# PIC_POWER_MISC.net
KiCad netlist of a schematic drawn in Altium Designer
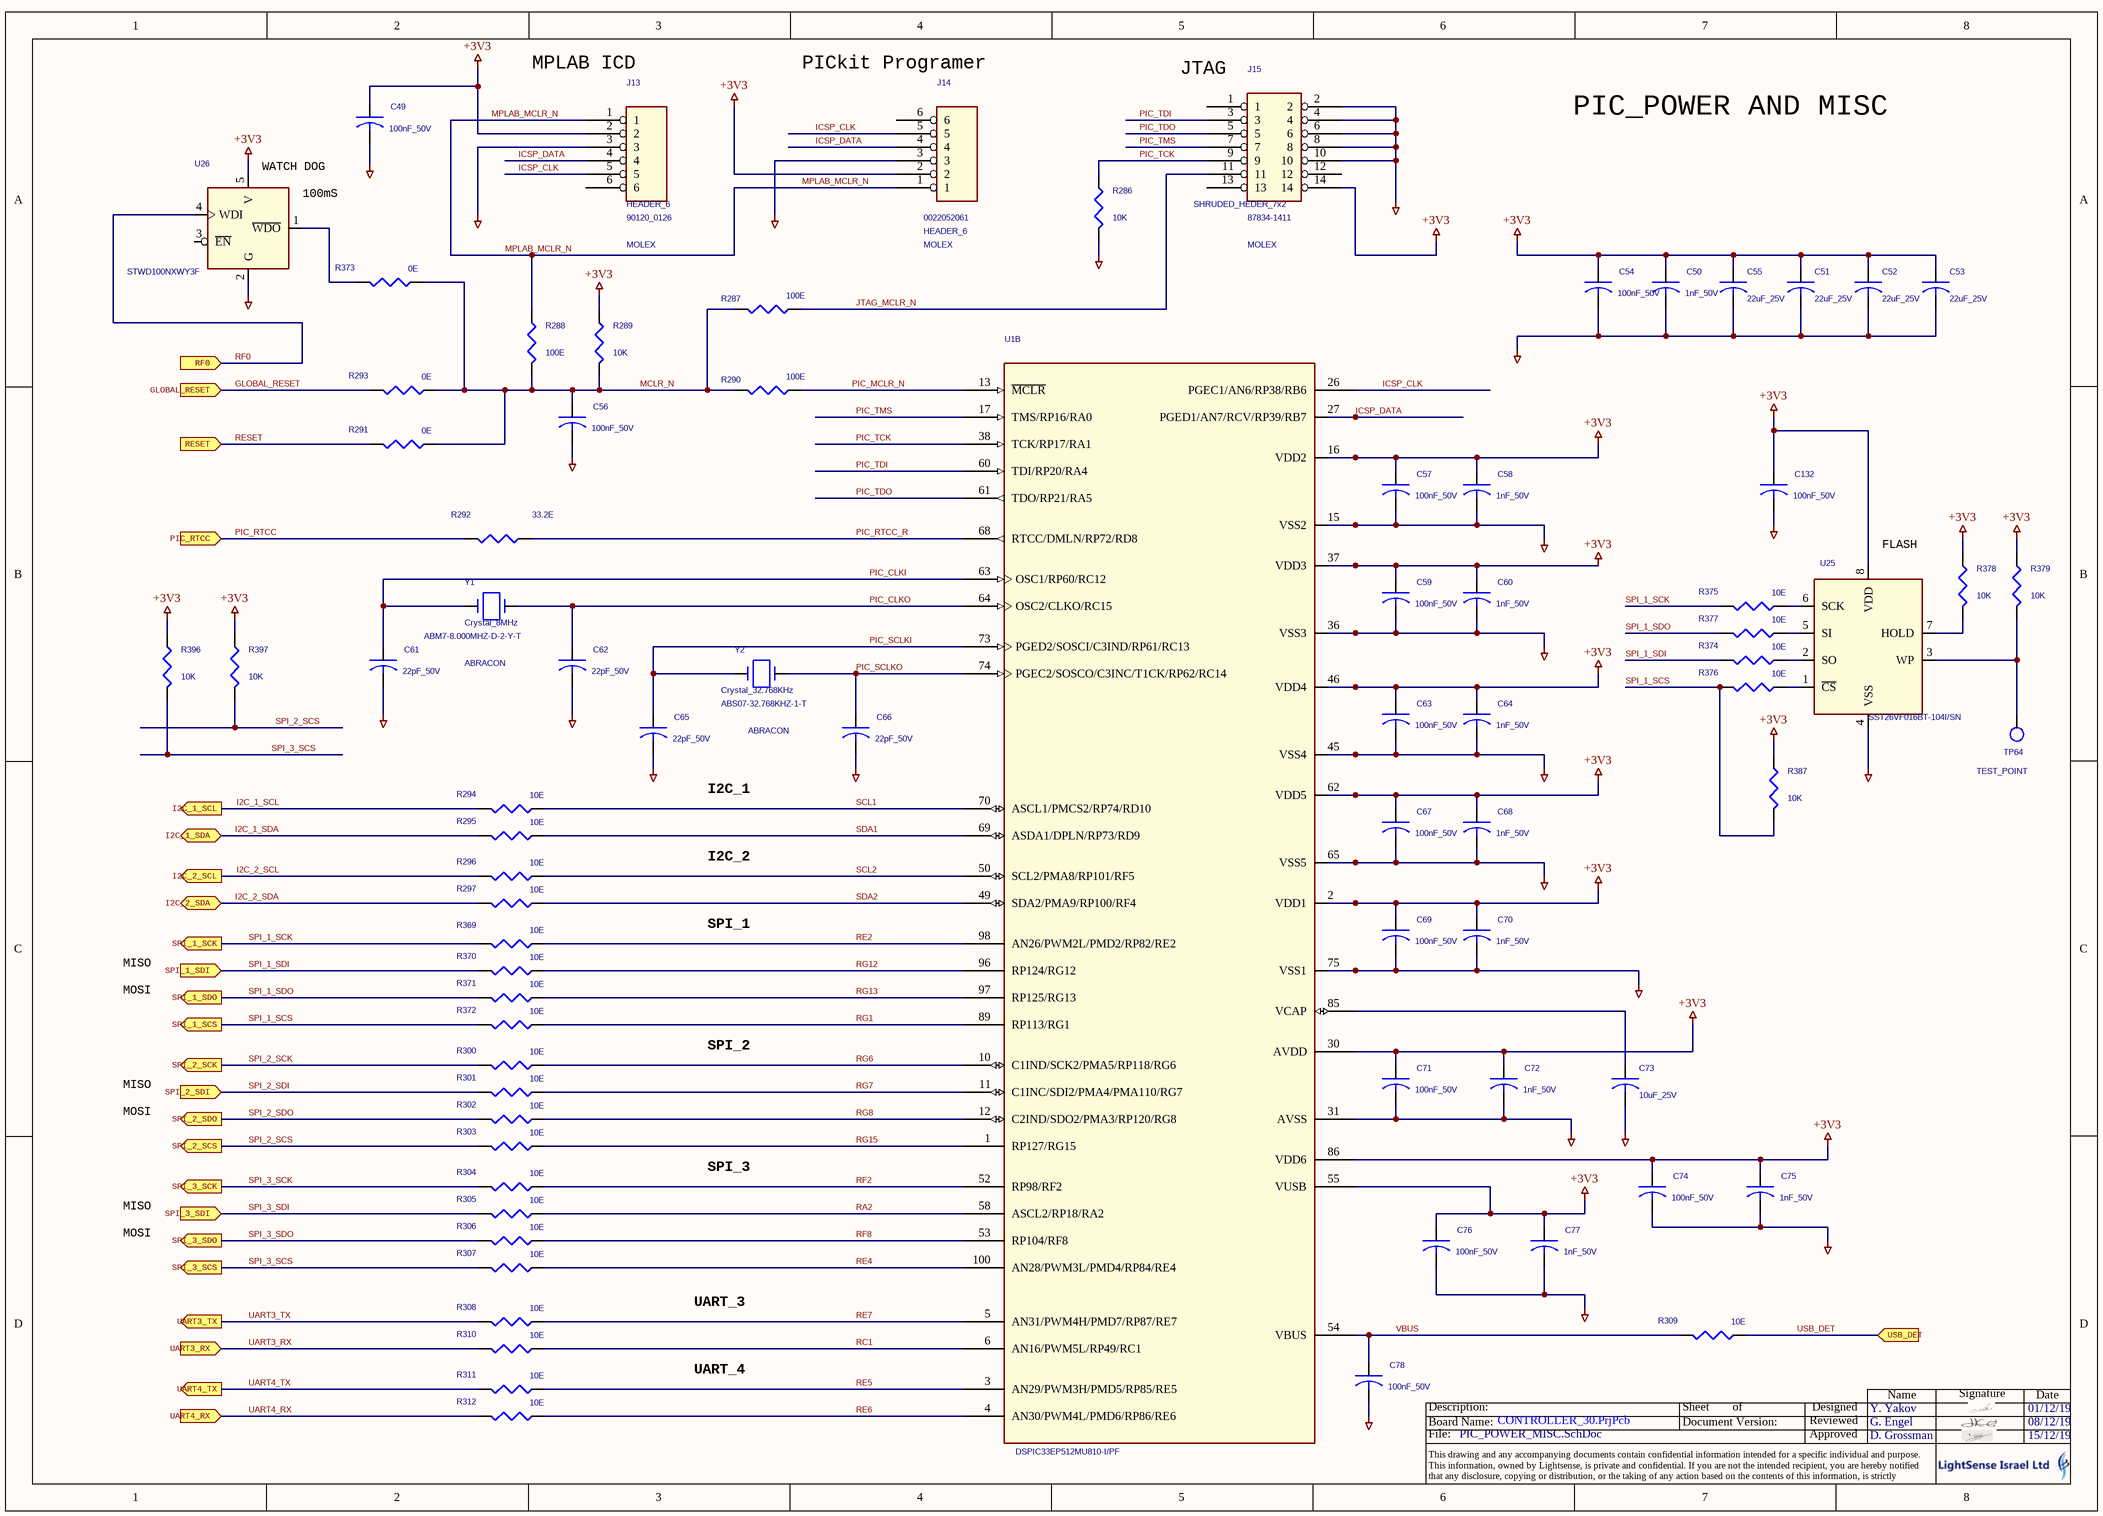
[diagram p0: PIC_POWER_MISC.SchDoc]

(export (version "E")
  (design (tool "Eeschema 10.0.6"))
  (components
    (comp (ref "C49")
      (value "100nF_50V")
      (footprint "0603")
      (description "CAP_SMT_0603_50V_X7R_10%")
      (fields (field (name "MFG") "KEMET"))
      (libsource (lib "*") (part "C"))
    )
    (comp (ref "C50")
      (value "1nF_50V")
      (footprint "0603")
      (description "CAP_SMT_0603_50V_X7R_10%")
      (fields (field (name "MFG") "KEMET"))
      (libsource (lib "*") (part "C"))
    )
    (comp (ref "C51")
      (value "22uF_25V")
      (footprint "1210")
      (description "CAP_SMT_1210_25V_X7R_10%")
      (fields (field (name "MFG") "KEMET"))
      (libsource (lib "*") (part "C"))
    )
    (comp (ref "C52")
      (value "22uF_25V")
      (footprint "1210")
      (description "CAP_SMT_1210_25V_X7R_10%")
      (fields (field (name "MFG") "KEMET"))
      (libsource (lib "*") (part "C"))
    )
    (comp (ref "C53")
      (value "22uF_25V")
      (footprint "1210")
      (description "CAP_SMT_1210_25V_X7R_10%")
      (fields (field (name "MFG") "KEMET"))
      (libsource (lib "*") (part "C"))
    )
    (comp (ref "C54")
      (value "100nF_50V")
      (footprint "0603")
      (description "CAP_SMT_0603_50V_X7R_10%")
      (fields (field (name "MFG") "KEMET"))
      (libsource (lib "*") (part "C"))
    )
    (comp (ref "C55")
      (value "22uF_25V")
      (footprint "1210")
      (description "CAP_SMT_1210_25V_X7R_10%")
      (fields (field (name "MFG") "KEMET"))
      (libsource (lib "*") (part "C"))
    )
    (comp (ref "C56")
      (value "100nF_50V")
      (footprint "0603")
      (description "CAP_SMT_0603_50V_X7R_10%")
      (fields (field (name "MFG") "KEMET"))
      (libsource (lib "*") (part "C"))
    )
    (comp (ref "C57")
      (value "100nF_50V")
      (footprint "0603")
      (description "CAP_SMT_0603_50V_X7R_10%")
      (fields (field (name "MFG") "KEMET"))
      (libsource (lib "*") (part "C"))
    )
    (comp (ref "C58")
      (value "1nF_50V")
      (footprint "0603")
      (description "CAP_SMT_0603_50V_X7R_10%")
      (fields (field (name "MFG") "KEMET"))
      (libsource (lib "*") (part "C"))
    )
    (comp (ref "C59")
      (value "100nF_50V")
      (footprint "0603")
      (description "CAP_SMT_0603_50V_X7R_10%")
      (fields (field (name "MFG") "KEMET"))
      (libsource (lib "*") (part "C"))
    )
    (comp (ref "C60")
      (value "1nF_50V")
      (footprint "0603")
      (description "CAP_SMT_0603_50V_X7R_10%")
      (fields (field (name "MFG") "KEMET"))
      (libsource (lib "*") (part "C"))
    )
    (comp (ref "C61")
      (value "22pF_50V")
      (footprint "0603")
      (description "CAP_SMT_0603_50V_COG_10%")
      (fields (field (name "MFG") "KEMET"))
      (libsource (lib "*") (part "C"))
    )
    (comp (ref "C62")
      (value "22pF_50V")
      (footprint "0603")
      (description "CAP_SMT_0603_50V_COG_10%")
      (fields (field (name "MFG") "KEMET"))
      (libsource (lib "*") (part "C"))
    )
    (comp (ref "C63")
      (value "100nF_50V")
      (footprint "0603")
      (description "CAP_SMT_0603_50V_X7R_10%")
      (fields (field (name "MFG") "KEMET"))
      (libsource (lib "*") (part "C"))
    )
    (comp (ref "C64")
      (value "1nF_50V")
      (footprint "0603")
      (description "CAP_SMT_0603_50V_X7R_10%")
      (fields (field (name "MFG") "KEMET"))
      (libsource (lib "*") (part "C"))
    )
    (comp (ref "C65")
      (value "22pF_50V")
      (footprint "0603")
      (description "CAP_SMT_0603_50V_COG_10%")
      (fields (field (name "MFG") "KEMET"))
      (libsource (lib "*") (part "C"))
    )
    (comp (ref "C66")
      (value "22pF_50V")
      (footprint "0603")
      (description "CAP_SMT_0603_50V_COG_10%")
      (fields (field (name "MFG") "KEMET"))
      (libsource (lib "*") (part "C"))
    )
    (comp (ref "C67")
      (value "100nF_50V")
      (footprint "0603")
      (description "CAP_SMT_0603_50V_X7R_10%")
      (fields (field (name "MFG") "KEMET"))
      (libsource (lib "*") (part "C"))
    )
    (comp (ref "C68")
      (value "1nF_50V")
      (footprint "0603")
      (description "CAP_SMT_0603_50V_X7R_10%")
      (fields (field (name "MFG") "KEMET"))
      (libsource (lib "*") (part "C"))
    )
    (comp (ref "C69")
      (value "100nF_50V")
      (footprint "0603")
      (description "CAP_SMT_0603_50V_X7R_10%")
      (fields (field (name "MFG") "KEMET"))
      (libsource (lib "*") (part "C"))
    )
    (comp (ref "C70")
      (value "1nF_50V")
      (footprint "0603")
      (description "CAP_SMT_0603_50V_X7R_10%")
      (fields (field (name "MFG") "KEMET"))
      (libsource (lib "*") (part "C"))
    )
    (comp (ref "C71")
      (value "100nF_50V")
      (footprint "0603")
      (description "CAP_SMT_0603_50V_X7R_10%")
      (fields (field (name "MFG") "KEMET"))
      (libsource (lib "*") (part "C"))
    )
    (comp (ref "C72")
      (value "1nF_50V")
      (footprint "0603")
      (description "CAP_SMT_0603_50V_X7R_10%")
      (fields (field (name "MFG") "KEMET"))
      (libsource (lib "*") (part "C"))
    )
    (comp (ref "C73")
      (value "10uF_25V")
      (footprint "1206")
      (description "CAP_SMT_1206_25V_X7R_10%")
      (fields (field (name "MFG") "KEMET"))
      (libsource (lib "*") (part "C"))
    )
    (comp (ref "C74")
      (value "100nF_50V")
      (footprint "0603")
      (description "CAP_SMT_0603_50V_X7R_10%")
      (fields (field (name "MFG") "KEMET"))
      (libsource (lib "*") (part "C"))
    )
    (comp (ref "C75")
      (value "1nF_50V")
      (footprint "0603")
      (description "CAP_SMT_0603_50V_X7R_10%")
      (fields (field (name "MFG") "KEMET"))
      (libsource (lib "*") (part "C"))
    )
    (comp (ref "C76")
      (value "100nF_50V")
      (footprint "0603")
      (description "CAP_SMT_0603_50V_X7R_10%")
      (fields (field (name "MFG") "KEMET"))
      (libsource (lib "*") (part "C"))
    )
    (comp (ref "C77")
      (value "1nF_50V")
      (footprint "0603")
      (description "CAP_SMT_0603_50V_X7R_10%")
      (fields (field (name "MFG") "KEMET"))
      (libsource (lib "*") (part "C"))
    )
    (comp (ref "C78")
      (value "100nF_50V")
      (footprint "0603")
      (description "CAP_SMT_0603_50V_X7R_10%")
      (fields (field (name "MFG") "KEMET"))
      (libsource (lib "*") (part "C"))
    )
    (comp (ref "C132")
      (value "100nF_50V")
      (footprint "0603")
      (description "CAP_SMT_0603_50V_X7R_10%")
      (fields (field (name "MFG") "KEMET"))
      (libsource (lib "*") (part "C"))
    )
    (comp (ref "J13")
      (value "HEADER_6")
      (footprint "HEADER_6PIN_100mil")
      (fields (field (name "MFG") "MOLEX") (field (name "MFG_PN") "90120_0126"))
      (libsource (lib "*") (part "HEADER 6"))
    )
    (comp (ref "J14")
      (value "HEADER_6")
      (footprint "HEADER_6PIN_100mil")
      (fields (field (name "MFG_PN") "0022052061") (field (name "MFG") "MOLEX"))
      (libsource (lib "") (part "HEADER 6_1"))
    )
    (comp (ref "J15")
      (value "SHRUDED_HEDER_7x2")
      (footprint "SH_HEAD_2x7PIN_100mil")
      (fields (field (name "MFG") "MOLEX") (field (name "MFG_PN") "87834-1411"))
      (libsource (lib "*") (part "HEDER_7x2"))
    )
    (comp (ref "R286")
      (value "10K")
      (footprint "0603")
      (fields (field (name "MFG") "YAGEO"))
      (libsource (lib "*") (part "R_Dup1"))
    )
    (comp (ref "R287")
      (value "100E")
      (footprint "0603")
      (fields (field (name "MFG") "YAGEO"))
      (libsource (lib "*") (part "R_Dup1"))
    )
    (comp (ref "R288")
      (value "100E")
      (footprint "0603")
      (fields (field (name "MFG") "YAGEO"))
      (libsource (lib "*") (part "R_Dup1"))
    )
    (comp (ref "R289")
      (value "10K")
      (footprint "0603")
      (fields (field (name "MFG") "YAGEO"))
      (libsource (lib "*") (part "R_Dup1"))
    )
    (comp (ref "R290")
      (value "100E")
      (footprint "0603")
      (fields (field (name "MFG") "YAGEO"))
      (libsource (lib "*") (part "R_Dup1"))
    )
    (comp (ref "R291")
      (value "0E")
      (footprint "0603")
      (fields (field (name "MFG") "YAGEO"))
      (libsource (lib "*") (part "R_Dup1"))
    )
    (comp (ref "R292")
      (value "33.2E")
      (footprint "0603")
      (fields (field (name "MFG") "YAGEO"))
      (libsource (lib "*") (part "R_Dup1"))
    )
    (comp (ref "R293")
      (value "0E")
      (footprint "0603")
      (fields (field (name "MFG") "YAGEO"))
      (libsource (lib "*") (part "R_Dup1"))
    )
    (comp (ref "R294")
      (value "10E")
      (footprint "0603")
      (fields (field (name "MFG") "YAGEO"))
      (libsource (lib "*") (part "R_Dup1"))
    )
    (comp (ref "R295")
      (value "10E")
      (footprint "0603")
      (fields (field (name "MFG") "YAGEO"))
      (libsource (lib "*") (part "R_Dup1"))
    )
    (comp (ref "R296")
      (value "10E")
      (footprint "0603")
      (fields (field (name "MFG") "YAGEO"))
      (libsource (lib "*") (part "R_Dup1"))
    )
    (comp (ref "R297")
      (value "10E")
      (footprint "0603")
      (fields (field (name "MFG") "YAGEO"))
      (libsource (lib "*") (part "R_Dup1"))
    )
    (comp (ref "R300")
      (value "10E")
      (footprint "0603")
      (fields (field (name "MFG") "YAGEO"))
      (libsource (lib "*") (part "R_Dup1"))
    )
    (comp (ref "R301")
      (value "10E")
      (footprint "0603")
      (fields (field (name "MFG") "YAGEO"))
      (libsource (lib "*") (part "R_Dup1"))
    )
    (comp (ref "R302")
      (value "10E")
      (footprint "0603")
      (fields (field (name "MFG") "YAGEO"))
      (libsource (lib "*") (part "R_Dup1"))
    )
    (comp (ref "R303")
      (value "10E")
      (footprint "0603")
      (fields (field (name "MFG") "YAGEO"))
      (libsource (lib "*") (part "R_Dup1"))
    )
    (comp (ref "R304")
      (value "10E")
      (footprint "0603")
      (fields (field (name "MFG") "YAGEO"))
      (libsource (lib "*") (part "R_Dup1"))
    )
    (comp (ref "R305")
      (value "10E")
      (footprint "0603")
      (fields (field (name "MFG") "YAGEO"))
      (libsource (lib "*") (part "R_Dup1"))
    )
    (comp (ref "R306")
      (value "10E")
      (footprint "0603")
      (fields (field (name "MFG") "YAGEO"))
      (libsource (lib "*") (part "R_Dup1"))
    )
    (comp (ref "R307")
      (value "10E")
      (footprint "0603")
      (fields (field (name "MFG") "YAGEO"))
      (libsource (lib "*") (part "R_Dup1"))
    )
    (comp (ref "R308")
      (value "10E")
      (footprint "0603")
      (fields (field (name "MFG") "YAGEO"))
      (libsource (lib "*") (part "R_Dup1"))
    )
    (comp (ref "R309")
      (value "10E")
      (footprint "0603")
      (fields (field (name "MFG") "YAGEO"))
      (libsource (lib "*") (part "R_Dup1"))
    )
    (comp (ref "R310")
      (value "10E")
      (footprint "0603")
      (fields (field (name "MFG") "YAGEO"))
      (libsource (lib "*") (part "R_Dup1"))
    )
    (comp (ref "R311")
      (value "10E")
      (footprint "0603")
      (fields (field (name "MFG") "YAGEO"))
      (libsource (lib "*") (part "R_Dup1"))
    )
    (comp (ref "R312")
      (value "10E")
      (footprint "0603")
      (fields (field (name "MFG") "YAGEO"))
      (libsource (lib "*") (part "R_Dup1"))
    )
    (comp (ref "R369")
      (value "10E")
      (footprint "0603")
      (fields (field (name "MFG") "YAGEO"))
      (libsource (lib "*") (part "R_Dup1"))
    )
    (comp (ref "R370")
      (value "10E")
      (footprint "0603")
      (fields (field (name "MFG") "YAGEO"))
      (libsource (lib "*") (part "R_Dup1"))
    )
    (comp (ref "R371")
      (value "10E")
      (footprint "0603")
      (fields (field (name "MFG") "YAGEO"))
      (libsource (lib "*") (part "R_Dup1"))
    )
    (comp (ref "R372")
      (value "10E")
      (footprint "0603")
      (fields (field (name "MFG") "YAGEO"))
      (libsource (lib "*") (part "R_Dup1"))
    )
    (comp (ref "R373")
      (value "0E")
      (footprint "0603")
      (fields (field (name "MFG") "YAGEO"))
      (libsource (lib "*") (part "R_Dup1"))
    )
    (comp (ref "R374")
      (value "10E")
      (footprint "0603")
      (fields (field (name "MFG") "YAGEO"))
      (libsource (lib "*") (part "R_Dup1"))
    )
    (comp (ref "R375")
      (value "10E")
      (footprint "0603")
      (fields (field (name "MFG") "YAGEO"))
      (libsource (lib "*") (part "R_Dup1"))
    )
    (comp (ref "R376")
      (value "10E")
      (footprint "0603")
      (fields (field (name "MFG") "YAGEO"))
      (libsource (lib "*") (part "R_Dup1"))
    )
    (comp (ref "R377")
      (value "10E")
      (footprint "0603")
      (fields (field (name "MFG") "YAGEO"))
      (libsource (lib "*") (part "R_Dup1"))
    )
    (comp (ref "R378")
      (value "10K")
      (footprint "0603")
      (fields (field (name "MFG") "YAGEO"))
      (libsource (lib "*") (part "R_Dup1"))
    )
    (comp (ref "R379")
      (value "10K")
      (footprint "0603")
      (fields (field (name "MFG") "YAGEO"))
      (libsource (lib "*") (part "R_Dup1"))
    )
    (comp (ref "R387")
      (value "10K")
      (footprint "0603")
      (fields (field (name "MFG") "YAGEO"))
      (libsource (lib "*") (part "R_Dup1"))
    )
    (comp (ref "R396")
      (value "10K")
      (footprint "0603")
      (fields (field (name "MFG") "YAGEO"))
      (libsource (lib "*") (part "R_Dup1"))
    )
    (comp (ref "R397")
      (value "10K")
      (footprint "0603")
      (fields (field (name "MFG") "YAGEO"))
      (libsource (lib "*") (part "R_Dup1"))
    )
    (comp (ref "TP64")
      (value "TEST_POINT")
      (footprint "TH_1mm")
      (libsource (lib "*") (part "T POINT R_Dup1"))
    )
    (comp (ref "U1")
      (value "DSPIC33EP512MU810-I/PF")
      (footprint "TQFP_100")
      (fields (field (name "MFG") "MICROCHIP"))
      (libsource (lib "*") (part "DSPIC33EP512MU810-I/PF_0"))
    )
    (comp (ref "U25")
      (value "SST26VF016BT-104I/SN")
      (footprint "SOIC_8")
      (fields (field (name "MFG") "MICROCHIP"))
      (libsource (lib "*") (part "SST26VF016BT-104I/SN"))
    )
    (comp (ref "U26")
      (value "STWD100NXWY3F")
      (footprint "SOT_23_5")
      (description "WATCHDOG_100ms_SOT_23_5")
      (fields (field (name "MFG") "ST"))
      (libsource (lib "*") (part "STWD100NXWY3F"))
    )
    (comp (ref "Y1")
      (value "Crystal_8MHz")
      (footprint "ABM7_SMD_2PIN")
      (fields (field (name "MFG_PN") "ABM7-8.000MHZ-D-2-Y-T") (field (name "MFG") "ABRACON"))
      (libsource (lib "*") (part "Quartz"))
    )
    (comp (ref "Y2")
      (value "Crystal_32.768KHz")
      (footprint "ABS07_SMD_2PIN")
      (fields (field (name "MFG") "ABRACON") (field (name "MFG_PN") "ABS07-32.768KHZ-1-T"))
      (libsource (lib "*") (part "Quartz"))
    )
  )
  (nets
    (net (code "1") (name "+3V3") (class "Default")
      (node (ref "C132") (pin "1") (pinfunction "1_1") (pintype "passive"))
      (node (ref "C49") (pin "1") (pinfunction "1_1") (pintype "passive"))
      (node (ref "C50") (pin "1") (pinfunction "1_1") (pintype "passive"))
      (node (ref "C51") (pin "1") (pinfunction "1_1") (pintype "passive"))
      (node (ref "C52") (pin "1") (pinfunction "1_1") (pintype "passive"))
      (node (ref "C53") (pin "1") (pinfunction "1_1") (pintype "passive"))
      (node (ref "C54") (pin "1") (pinfunction "1_1") (pintype "passive"))
      (node (ref "C55") (pin "1") (pinfunction "1_1") (pintype "passive"))
      (node (ref "C57") (pin "1") (pinfunction "1_1") (pintype "passive"))
      (node (ref "C58") (pin "1") (pinfunction "1_1") (pintype "passive"))
      (node (ref "C59") (pin "1") (pinfunction "1_1") (pintype "passive"))
      (node (ref "C60") (pin "1") (pinfunction "1_1") (pintype "passive"))
      (node (ref "C63") (pin "1") (pinfunction "1_1") (pintype "passive"))
      (node (ref "C64") (pin "1") (pinfunction "1_1") (pintype "passive"))
      (node (ref "C67") (pin "1") (pinfunction "1_1") (pintype "passive"))
      (node (ref "C68") (pin "1") (pinfunction "1_1") (pintype "passive"))
      (node (ref "C69") (pin "1") (pinfunction "1_1") (pintype "passive"))
      (node (ref "C70") (pin "1") (pinfunction "1_1") (pintype "passive"))
      (node (ref "C71") (pin "1") (pinfunction "1_1") (pintype "passive"))
      (node (ref "C72") (pin "1") (pinfunction "1_1") (pintype "passive"))
      (node (ref "C74") (pin "1") (pinfunction "1_1") (pintype "passive"))
      (node (ref "C75") (pin "1") (pinfunction "1_1") (pintype "passive"))
      (node (ref "C76") (pin "1") (pinfunction "1_1") (pintype "passive"))
      (node (ref "C77") (pin "1") (pinfunction "1_1") (pintype "passive"))
      (node (ref "J13") (pin "2") (pinfunction "2_2") (pintype "passive"))
      (node (ref "J14") (pin "2") (pinfunction "2_2") (pintype "passive"))
      (node (ref "J15") (pin "14") (pinfunction "14_14") (pintype "passive"))
      (node (ref "R289") (pin "1") (pinfunction "1_1") (pintype "passive"))
      (node (ref "R378") (pin "1") (pinfunction "1_1") (pintype "passive"))
      (node (ref "R379") (pin "1") (pinfunction "1_1") (pintype "passive"))
      (node (ref "R387") (pin "1") (pinfunction "1_1") (pintype "passive"))
      (node (ref "R396") (pin "1") (pinfunction "1_1") (pintype "passive"))
      (node (ref "R397") (pin "1") (pinfunction "1_1") (pintype "passive"))
      (node (ref "U1") (pin "16") (pinfunction "VDD2_16") (pintype "power_in"))
      (node (ref "U1") (pin "2") (pinfunction "VDD1_2") (pintype "power_in"))
      (node (ref "U1") (pin "30") (pinfunction "AVDD_30") (pintype "passive"))
      (node (ref "U1") (pin "37") (pinfunction "VDD3_37") (pintype "power_in"))
      (node (ref "U1") (pin "46") (pinfunction "VDD4_46") (pintype "power_in"))
      (node (ref "U1") (pin "55") (pinfunction "VUSB_55") (pintype "passive"))
      (node (ref "U1") (pin "62") (pinfunction "VDD5_62") (pintype "power_in"))
      (node (ref "U1") (pin "86") (pinfunction "VDD6_86") (pintype "passive"))
      (node (ref "U25") (pin "8") (pinfunction "VDD_8") (pintype "passive"))
      (node (ref "U26") (pin "5") (pinfunction "V_5") (pintype "passive"))
    )
    (net (code "2") (name "/GLOBAL_RESET") (class "Default")
      (node (ref "R293") (pin "2") (pinfunction "2_2") (pintype "passive"))
    )
    (net (code "3") (name "/I2C_1_SCL") (class "Default")
      (node (ref "R294") (pin "2") (pinfunction "2_2") (pintype "passive"))
    )
    (net (code "4") (name "/I2C_1_SDA") (class "Default")
      (node (ref "R295") (pin "2") (pinfunction "2_2") (pintype "passive"))
    )
    (net (code "5") (name "/I2C_2_SCL") (class "Default")
      (node (ref "R296") (pin "2") (pinfunction "2_2") (pintype "passive"))
    )
    (net (code "6") (name "/I2C_2_SDA") (class "Default")
      (node (ref "R297") (pin "2") (pinfunction "2_2") (pintype "passive"))
    )
    (net (code "7") (name "/ICSP_CLK") (class "Default")
      (node (ref "J13") (pin "5") (pinfunction "5_5") (pintype "passive"))
      (node (ref "J14") (pin "5") (pinfunction "5_5") (pintype "passive"))
      (node (ref "U1") (pin "26") (pinfunction "PGEC1/AN6/RP38/RB6_26") (pintype "passive"))
    )
    (net (code "8") (name "/ICSP_DATA") (class "Default")
      (node (ref "J13") (pin "4") (pinfunction "4_4") (pintype "passive"))
      (node (ref "J14") (pin "4") (pinfunction "4_4") (pintype "passive"))
      (node (ref "U1") (pin "27") (pinfunction "PGED1/AN7/RCV/RP39/RB7_27") (pintype "passive"))
    )
    (net (code "9") (name "/JTAG_MCLR_N") (class "Default")
      (node (ref "J15") (pin "11") (pinfunction "11_11") (pintype "passive"))
      (node (ref "R287") (pin "1") (pinfunction "1_1") (pintype "passive"))
    )
    (net (code "10") (name "/MCLR_N") (class "Default")
      (node (ref "C56") (pin "1") (pinfunction "1_1") (pintype "passive"))
      (node (ref "R287") (pin "2") (pinfunction "2_2") (pintype "passive"))
      (node (ref "R288") (pin "2") (pinfunction "2_2") (pintype "passive"))
      (node (ref "R289") (pin "2") (pinfunction "2_2") (pintype "passive"))
      (node (ref "R290") (pin "2") (pinfunction "2_2") (pintype "passive"))
      (node (ref "R291") (pin "1") (pinfunction "1_1") (pintype "passive"))
      (node (ref "R293") (pin "1") (pinfunction "1_1") (pintype "passive"))
      (node (ref "R373") (pin "1") (pinfunction "1_1") (pintype "passive"))
    )
    (net (code "11") (name "/MPLAB_MCLR_N") (class "Default")
      (node (ref "J13") (pin "1") (pinfunction "1_1") (pintype "passive"))
      (node (ref "J14") (pin "1") (pinfunction "1_1") (pintype "passive"))
      (node (ref "R288") (pin "1") (pinfunction "1_1") (pintype "passive"))
    )
    (net (code "12") (name "/PIC_CLKI") (class "Default")
      (node (ref "C61") (pin "1") (pinfunction "1_1") (pintype "passive"))
      (node (ref "U1") (pin "63") (pinfunction "OSC1/RP60/RC12_63") (pintype "input"))
      (node (ref "Y1") (pin "1") (pinfunction "1_1") (pintype "passive"))
    )
    (net (code "13") (name "/PIC_CLKO") (class "Default")
      (node (ref "C62") (pin "1") (pinfunction "1_1") (pintype "passive"))
      (node (ref "U1") (pin "64") (pinfunction "OSC2/CLKO/RC15_64") (pintype "input"))
      (node (ref "Y1") (pin "2") (pinfunction "2_2") (pintype "passive"))
    )
    (net (code "14") (name "/PIC_MCLR_N") (class "Default")
      (node (ref "R290") (pin "1") (pinfunction "1_1") (pintype "passive"))
      (node (ref "U1") (pin "13") (pinfunction "~{MCLR}_13") (pintype "input"))
    )
    (net (code "15") (name "/PIC_RTCC") (class "Default")
      (node (ref "R292") (pin "2") (pinfunction "2_2") (pintype "passive"))
    )
    (net (code "16") (name "/PIC_RTCC_R") (class "Default")
      (node (ref "R292") (pin "1") (pinfunction "1_1") (pintype "passive"))
      (node (ref "U1") (pin "68") (pinfunction "RTCC/DMLN/RP72/RD8_68") (pintype "output"))
    )
    (net (code "17") (name "/PIC_SCLKI") (class "Default")
      (node (ref "C65") (pin "1") (pinfunction "1_1") (pintype "passive"))
      (node (ref "U1") (pin "73") (pinfunction "PGED2/SOSCI/C3IND/RP61/RC13_73") (pintype "input"))
      (node (ref "Y2") (pin "1") (pinfunction "1_1") (pintype "passive"))
    )
    (net (code "18") (name "/PIC_SCLKO") (class "Default")
      (node (ref "C66") (pin "1") (pinfunction "1_1") (pintype "passive"))
      (node (ref "U1") (pin "74") (pinfunction "PGEC2/SOSCO/C3INC/T1CK/RP62/RC14_74") (pintype "input"))
      (node (ref "Y2") (pin "2") (pinfunction "2_2") (pintype "passive"))
    )
    (net (code "19") (name "/PIC_TCK") (class "Default")
      (node (ref "J15") (pin "9") (pinfunction "9_9") (pintype "passive"))
      (node (ref "R286") (pin "1") (pinfunction "1_1") (pintype "passive"))
      (node (ref "U1") (pin "38") (pinfunction "TCK/RP17/RA1_38") (pintype "input"))
    )
    (net (code "20") (name "/PIC_TDI") (class "Default")
      (node (ref "J15") (pin "3") (pinfunction "3_3") (pintype "passive"))
      (node (ref "U1") (pin "60") (pinfunction "TDI/RP20/RA4_60") (pintype "input"))
    )
    (net (code "21") (name "/PIC_TDO") (class "Default")
      (node (ref "J15") (pin "5") (pinfunction "5_5") (pintype "passive"))
      (node (ref "U1") (pin "61") (pinfunction "TDO/RP21/RA5_61") (pintype "output"))
    )
    (net (code "22") (name "/PIC_TMS") (class "Default")
      (node (ref "J15") (pin "7") (pinfunction "7_7") (pintype "passive"))
      (node (ref "U1") (pin "17") (pinfunction "TMS/RP16/RA0_17") (pintype "input"))
    )
    (net (code "23") (name "/RA2") (class "Default")
      (node (ref "R305") (pin "1") (pinfunction "1_1") (pintype "passive"))
      (node (ref "U1") (pin "58") (pinfunction "ASCL2/RP18/RA2_58") (pintype "passive"))
    )
    (net (code "24") (name "/RC1") (class "Default")
      (node (ref "R310") (pin "1") (pinfunction "1_1") (pintype "passive"))
      (node (ref "U1") (pin "6") (pinfunction "AN16/PWM5L/RP49/RC1_6") (pintype "passive"))
    )
    (net (code "25") (name "/RE2") (class "Default")
      (node (ref "R369") (pin "1") (pinfunction "1_1") (pintype "passive"))
      (node (ref "U1") (pin "98") (pinfunction "AN26/PWM2L/PMD2/RP82/RE2_98") (pintype "passive"))
    )
    (net (code "26") (name "/RE4") (class "Default")
      (node (ref "R307") (pin "1") (pinfunction "1_1") (pintype "passive"))
      (node (ref "U1") (pin "100") (pinfunction "AN28/PWM3L/PMD4/RP84/RE4_100") (pintype "passive"))
    )
    (net (code "27") (name "/RE5") (class "Default")
      (node (ref "R311") (pin "1") (pinfunction "1_1") (pintype "passive"))
      (node (ref "U1") (pin "3") (pinfunction "AN29/PWM3H/PMD5/RP85/RE5_3") (pintype "passive"))
    )
    (net (code "28") (name "/RE6") (class "Default")
      (node (ref "R312") (pin "1") (pinfunction "1_1") (pintype "passive"))
      (node (ref "U1") (pin "4") (pinfunction "AN30/PWM4L/PMD6/RP86/RE6_4") (pintype "passive"))
    )
    (net (code "29") (name "/RE7") (class "Default")
      (node (ref "R308") (pin "1") (pinfunction "1_1") (pintype "passive"))
      (node (ref "U1") (pin "5") (pinfunction "AN31/PWM4H/PMD7/RP87/RE7_5") (pintype "passive"))
    )
    (net (code "30") (name "/RESET") (class "Default")
      (node (ref "R291") (pin "2") (pinfunction "2_2") (pintype "passive"))
    )
    (net (code "31") (name "/RF0") (class "Default")
      (node (ref "U26") (pin "4") (pinfunction "WDI_4") (pintype "passive"))
    )
    (net (code "32") (name "/RF2") (class "Default")
      (node (ref "R304") (pin "1") (pinfunction "1_1") (pintype "passive"))
      (node (ref "U1") (pin "52") (pinfunction "RP98/RF2_52") (pintype "passive"))
    )
    (net (code "33") (name "/RF8") (class "Default")
      (node (ref "R306") (pin "1") (pinfunction "1_1") (pintype "passive"))
      (node (ref "U1") (pin "53") (pinfunction "RP104/RF8_53") (pintype "passive"))
    )
    (net (code "34") (name "/RG1") (class "Default")
      (node (ref "R372") (pin "1") (pinfunction "1_1") (pintype "passive"))
      (node (ref "U1") (pin "89") (pinfunction "RP113/RG1_89") (pintype "passive"))
    )
    (net (code "35") (name "/RG6") (class "Default")
      (node (ref "R300") (pin "1") (pinfunction "1_1") (pintype "passive"))
      (node (ref "U1") (pin "10") (pinfunction "C1IND/SCK2/PMA5/RP118/RG6_10") (pintype "bidirectional"))
    )
    (net (code "36") (name "/RG7") (class "Default")
      (node (ref "R301") (pin "1") (pinfunction "1_1") (pintype "passive"))
      (node (ref "U1") (pin "11") (pinfunction "C1INC/SDI2/PMA4/PMA110/RG7_11") (pintype "bidirectional"))
    )
    (net (code "37") (name "/RG8") (class "Default")
      (node (ref "R302") (pin "1") (pinfunction "1_1") (pintype "passive"))
      (node (ref "U1") (pin "12") (pinfunction "C2IND/SDO2/PMA3/RP120/RG8_12") (pintype "bidirectional"))
    )
    (net (code "38") (name "/RG12") (class "Default")
      (node (ref "R370") (pin "1") (pinfunction "1_1") (pintype "passive"))
      (node (ref "U1") (pin "96") (pinfunction "RP124/RG12_96") (pintype "passive"))
    )
    (net (code "39") (name "/RG13") (class "Default")
      (node (ref "R371") (pin "1") (pinfunction "1_1") (pintype "passive"))
      (node (ref "U1") (pin "97") (pinfunction "RP125/RG13_97") (pintype "passive"))
    )
    (net (code "40") (name "/RG15") (class "Default")
      (node (ref "R303") (pin "1") (pinfunction "1_1") (pintype "passive"))
      (node (ref "U1") (pin "1") (pinfunction "RP127/RG15_1") (pintype "passive"))
    )
    (net (code "41") (name "/SCL1") (class "Default")
      (node (ref "R294") (pin "1") (pinfunction "1_1") (pintype "passive"))
      (node (ref "U1") (pin "70") (pinfunction "ASCL1/PMCS2/RP74/RD10_70") (pintype "bidirectional"))
    )
    (net (code "42") (name "/SCL2") (class "Default")
      (node (ref "R296") (pin "1") (pinfunction "1_1") (pintype "passive"))
      (node (ref "U1") (pin "50") (pinfunction "SCL2/PMA8/RP101/RF5_50") (pintype "bidirectional"))
    )
    (net (code "43") (name "/SDA1") (class "Default")
      (node (ref "R295") (pin "1") (pinfunction "1_1") (pintype "passive"))
      (node (ref "U1") (pin "69") (pinfunction "ASDA1/DPLN/RP73/RD9_69") (pintype "bidirectional"))
    )
    (net (code "44") (name "/SDA2") (class "Default")
      (node (ref "R297") (pin "1") (pinfunction "1_1") (pintype "passive"))
      (node (ref "U1") (pin "49") (pinfunction "SDA2/PMA9/RP100/RF4_49") (pintype "bidirectional"))
    )
    (net (code "45") (name "/SPI_1_SCK") (class "Default")
      (node (ref "R369") (pin "2") (pinfunction "2_2") (pintype "passive"))
      (node (ref "R375") (pin "2") (pinfunction "2_2") (pintype "passive"))
    )
    (net (code "46") (name "/SPI_1_SCS") (class "Default")
      (node (ref "R372") (pin "2") (pinfunction "2_2") (pintype "passive"))
      (node (ref "R376") (pin "2") (pinfunction "2_2") (pintype "passive"))
      (node (ref "R387") (pin "2") (pinfunction "2_2") (pintype "passive"))
    )
    (net (code "47") (name "/SPI_1_SDI") (class "Default")
      (node (ref "R370") (pin "2") (pinfunction "2_2") (pintype "passive"))
      (node (ref "R374") (pin "2") (pinfunction "2_2") (pintype "passive"))
    )
    (net (code "48") (name "/SPI_1_SDO") (class "Default")
      (node (ref "R371") (pin "2") (pinfunction "2_2") (pintype "passive"))
      (node (ref "R377") (pin "2") (pinfunction "2_2") (pintype "passive"))
    )
    (net (code "49") (name "/SPI_2_SCK") (class "Default")
      (node (ref "R300") (pin "2") (pinfunction "2_2") (pintype "passive"))
    )
    (net (code "50") (name "/SPI_2_SCS") (class "Default")
      (node (ref "R303") (pin "2") (pinfunction "2_2") (pintype "passive"))
      (node (ref "R397") (pin "2") (pinfunction "2_2") (pintype "passive"))
    )
    (net (code "51") (name "/SPI_2_SDI") (class "Default")
      (node (ref "R301") (pin "2") (pinfunction "2_2") (pintype "passive"))
    )
    (net (code "52") (name "/SPI_2_SDO") (class "Default")
      (node (ref "R302") (pin "2") (pinfunction "2_2") (pintype "passive"))
    )
    (net (code "53") (name "/SPI_3_SCK") (class "Default")
      (node (ref "R304") (pin "2") (pinfunction "2_2") (pintype "passive"))
    )
    (net (code "54") (name "/SPI_3_SCS") (class "Default")
      (node (ref "R307") (pin "2") (pinfunction "2_2") (pintype "passive"))
      (node (ref "R396") (pin "2") (pinfunction "2_2") (pintype "passive"))
    )
    (net (code "55") (name "/SPI_3_SDI") (class "Default")
      (node (ref "R305") (pin "2") (pinfunction "2_2") (pintype "passive"))
    )
    (net (code "56") (name "/SPI_3_SDO") (class "Default")
      (node (ref "R306") (pin "2") (pinfunction "2_2") (pintype "passive"))
    )
    (net (code "57") (name "/UART3_RX") (class "Default")
      (node (ref "R310") (pin "2") (pinfunction "2_2") (pintype "passive"))
    )
    (net (code "58") (name "/UART3_TX") (class "Default")
      (node (ref "R308") (pin "2") (pinfunction "2_2") (pintype "passive"))
    )
    (net (code "59") (name "/UART4_RX") (class "Default")
      (node (ref "R312") (pin "2") (pinfunction "2_2") (pintype "passive"))
    )
    (net (code "60") (name "/UART4_TX") (class "Default")
      (node (ref "R311") (pin "2") (pinfunction "2_2") (pintype "passive"))
    )
    (net (code "61") (name "/USB_DET") (class "Default")
      (node (ref "R309") (pin "1") (pinfunction "1_1") (pintype "passive"))
    )
    (net (code "62") (name "/VBUS") (class "Default")
      (node (ref "C78") (pin "1") (pinfunction "1_1") (pintype "passive"))
      (node (ref "R309") (pin "2") (pinfunction "2_2") (pintype "passive"))
      (node (ref "U1") (pin "54") (pinfunction "VBUS_54") (pintype "passive"))
    )
    (net (code "63") (name "GND_CPU") (class "Default")
      (node (ref "C132") (pin "2") (pinfunction "2_2") (pintype "passive"))
      (node (ref "C49") (pin "2") (pinfunction "2_2") (pintype "passive"))
      (node (ref "C50") (pin "2") (pinfunction "2_2") (pintype "passive"))
      (node (ref "C51") (pin "2") (pinfunction "2_2") (pintype "passive"))
      (node (ref "C52") (pin "2") (pinfunction "2_2") (pintype "passive"))
      (node (ref "C53") (pin "2") (pinfunction "2_2") (pintype "passive"))
      (node (ref "C54") (pin "2") (pinfunction "2_2") (pintype "passive"))
      (node (ref "C55") (pin "2") (pinfunction "2_2") (pintype "passive"))
      (node (ref "C56") (pin "2") (pinfunction "2_2") (pintype "passive"))
      (node (ref "C57") (pin "2") (pinfunction "2_2") (pintype "passive"))
      (node (ref "C58") (pin "2") (pinfunction "2_2") (pintype "passive"))
      (node (ref "C59") (pin "2") (pinfunction "2_2") (pintype "passive"))
      (node (ref "C60") (pin "2") (pinfunction "2_2") (pintype "passive"))
      (node (ref "C61") (pin "2") (pinfunction "2_2") (pintype "passive"))
      (node (ref "C62") (pin "2") (pinfunction "2_2") (pintype "passive"))
      (node (ref "C63") (pin "2") (pinfunction "2_2") (pintype "passive"))
      (node (ref "C64") (pin "2") (pinfunction "2_2") (pintype "passive"))
      (node (ref "C65") (pin "2") (pinfunction "2_2") (pintype "passive"))
      (node (ref "C66") (pin "2") (pinfunction "2_2") (pintype "passive"))
      (node (ref "C67") (pin "2") (pinfunction "2_2") (pintype "passive"))
      (node (ref "C68") (pin "2") (pinfunction "2_2") (pintype "passive"))
      (node (ref "C69") (pin "2") (pinfunction "2_2") (pintype "passive"))
      (node (ref "C70") (pin "2") (pinfunction "2_2") (pintype "passive"))
      (node (ref "C71") (pin "2") (pinfunction "2_2") (pintype "passive"))
      (node (ref "C72") (pin "2") (pinfunction "2_2") (pintype "passive"))
      (node (ref "C73") (pin "2") (pinfunction "2_2") (pintype "passive"))
      (node (ref "C74") (pin "2") (pinfunction "2_2") (pintype "passive"))
      (node (ref "C75") (pin "2") (pinfunction "2_2") (pintype "passive"))
      (node (ref "C76") (pin "2") (pinfunction "2_2") (pintype "passive"))
      (node (ref "C77") (pin "2") (pinfunction "2_2") (pintype "passive"))
      (node (ref "C78") (pin "2") (pinfunction "2_2") (pintype "passive"))
      (node (ref "J13") (pin "3") (pinfunction "3_3") (pintype "passive"))
      (node (ref "J14") (pin "3") (pinfunction "3_3") (pintype "passive"))
      (node (ref "J15") (pin "10") (pinfunction "10_10") (pintype "passive"))
      (node (ref "J15") (pin "2") (pinfunction "2_2") (pintype "passive"))
      (node (ref "J15") (pin "4") (pinfunction "4_4") (pintype "passive"))
      (node (ref "J15") (pin "6") (pinfunction "6_6") (pintype "passive"))
      (node (ref "J15") (pin "8") (pinfunction "8_8") (pintype "passive"))
      (node (ref "R286") (pin "2") (pinfunction "2_2") (pintype "passive"))
      (node (ref "U1") (pin "15") (pinfunction "VSS2_15") (pintype "power_in"))
      (node (ref "U1") (pin "31") (pinfunction "AVSS_31") (pintype "power_in"))
      (node (ref "U1") (pin "36") (pinfunction "VSS3_36") (pintype "power_in"))
      (node (ref "U1") (pin "45") (pinfunction "VSS4_45") (pintype "power_in"))
      (node (ref "U1") (pin "65") (pinfunction "VSS5_65") (pintype "power_in"))
      (node (ref "U1") (pin "75") (pinfunction "VSS1_75") (pintype "power_in"))
      (node (ref "U25") (pin "4") (pinfunction "VSS_4") (pintype "passive"))
      (node (ref "U26") (pin "2") (pinfunction "G_2") (pintype "passive"))
    )
    (net (code "64") (name "Net-(TP64-TP)") (class "Default")
      (node (ref "R379") (pin "2") (pinfunction "2_2") (pintype "passive"))
      (node (ref "TP64") (pin "1") (pinfunction "TP_1") (pintype "passive"))
      (node (ref "U25") (pin "3") (pinfunction "WP_3") (pintype "passive"))
    )
    (net (code "65") (name "Net-(U1B-VCAP)") (class "Default")
      (node (ref "C73") (pin "1") (pinfunction "1_1") (pintype "passive"))
      (node (ref "U1") (pin "85") (pinfunction "VCAP_85") (pintype "bidirectional"))
    )
    (net (code "66") (name "Net-(U25-HOLD)") (class "Default")
      (node (ref "R378") (pin "2") (pinfunction "2_2") (pintype "passive"))
      (node (ref "U25") (pin "7") (pinfunction "HOLD_7") (pintype "passive"))
    )
    (net (code "67") (name "Net-(U25-SCK)") (class "Default")
      (node (ref "R375") (pin "1") (pinfunction "1_1") (pintype "passive"))
      (node (ref "U25") (pin "6") (pinfunction "SCK_6") (pintype "passive"))
    )
    (net (code "68") (name "Net-(U25-SI)") (class "Default")
      (node (ref "R377") (pin "1") (pinfunction "1_1") (pintype "passive"))
      (node (ref "U25") (pin "5") (pinfunction "SI_5") (pintype "passive"))
    )
    (net (code "69") (name "Net-(U25-SO)") (class "Default")
      (node (ref "R374") (pin "1") (pinfunction "1_1") (pintype "passive"))
      (node (ref "U25") (pin "2") (pinfunction "SO_2") (pintype "passive"))
    )
    (net (code "70") (name "Net-(U25-~{CS})") (class "Default")
      (node (ref "R376") (pin "1") (pinfunction "1_1") (pintype "passive"))
      (node (ref "U25") (pin "1") (pinfunction "~{CS}_1") (pintype "passive"))
    )
    (net (code "71") (name "Net-(U26-~{WDO})") (class "Default")
      (node (ref "R373") (pin "2") (pinfunction "2_2") (pintype "passive"))
      (node (ref "U26") (pin "1") (pinfunction "~{WDO}_1") (pintype "open_collector"))
    )
    (net (code "72") (name "unconnected-(J13-Pad6)") (class "Default")
      (node (ref "J13") (pin "6") (pinfunction "6_6") (pintype "passive"))
    )
    (net (code "73") (name "unconnected-(J14-Pad6)") (class "Default")
      (node (ref "J14") (pin "6") (pinfunction "6_6") (pintype "passive"))
    )
    (net (code "74") (name "unconnected-(J15-Pad1)") (class "Default")
      (node (ref "J15") (pin "1") (pinfunction "1_1") (pintype "passive"))
    )
    (net (code "75") (name "unconnected-(J15-Pad12)") (class "Default")
      (node (ref "J15") (pin "12") (pinfunction "12_12") (pintype "passive"))
    )
    (net (code "76") (name "unconnected-(J15-Pad13)") (class "Default")
      (node (ref "J15") (pin "13") (pinfunction "13_13") (pintype "passive"))
    )
    (net (code "77") (name "unconnected-(U26-~{EN}-Pad3)") (class "Default")
      (node (ref "U26") (pin "3") (pinfunction "~{EN}_3") (pintype "passive"))
    )
  )
)
